# 180221_touchcircuit-2x1011.net
KiCad netlist of a schematic drawn in EAGLE
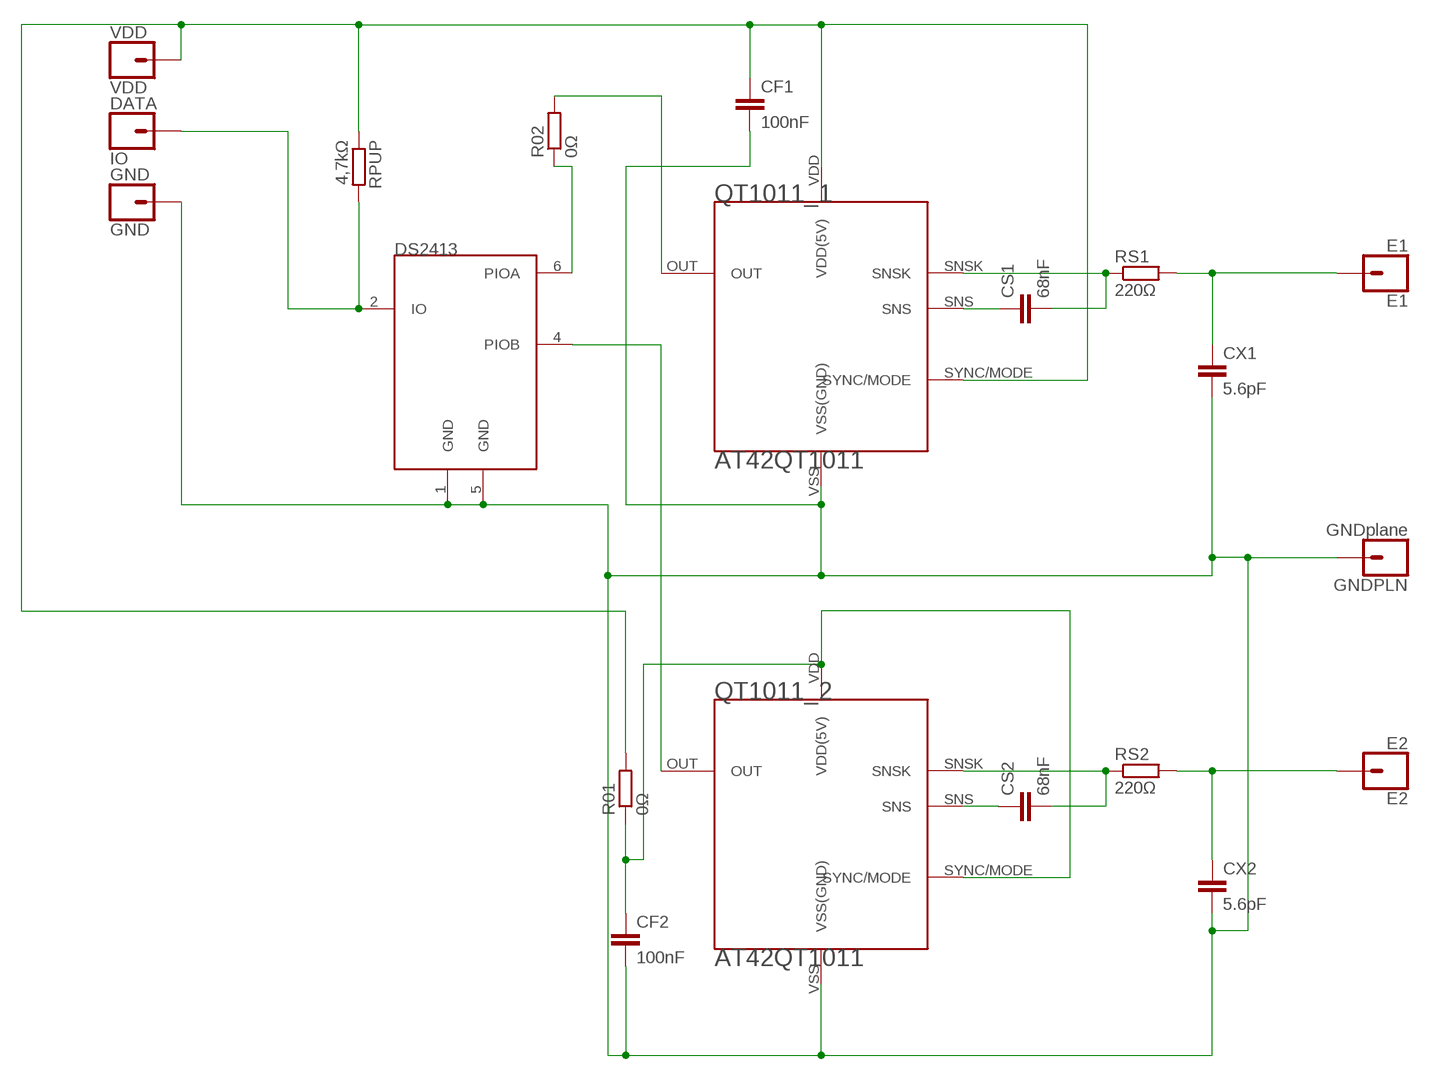
[diagram p0: schematic, sheet 1]

(export (version "E")
  (design (tool "Eeschema 10.0.6"))
  (components
    (comp (ref "CF1")
      (value "100nF")
      (footprint "eagle-import:C1206")
      (libsource (lib "eagle-import") (part "CC1206"))
    )
    (comp (ref "CF2")
      (value "100nF")
      (footprint "eagle-import:C1206")
      (libsource (lib "eagle-import") (part "CC1206"))
    )
    (comp (ref "CS1")
      (value "68nF")
      (footprint "eagle-import:C1206")
      (libsource (lib "eagle-import") (part "CC1206"))
    )
    (comp (ref "CS2")
      (value "68nF")
      (footprint "eagle-import:C1206")
      (libsource (lib "eagle-import") (part "CC1206"))
    )
    (comp (ref "CX1")
      (value "5.6pF")
      (footprint "eagle-import:C1206")
      (libsource (lib "eagle-import") (part "CC1206"))
    )
    (comp (ref "CX2")
      (value "5.6pF")
      (footprint "eagle-import:C1206")
      (libsource (lib "eagle-import") (part "CC1206"))
    )
    (comp (ref "DATA")
      (value "IO")
      (footprint "eagle-import:1X01")
      (libsource (lib "eagle-import") (part "CONN_01"))
    )
    (comp (ref "DS2413")
      (value "DS2413(TSOC6)")
      (footprint "eagle-import:TSOC6")
      (libsource (lib "eagle-import") (part "DS2413(TSOC6)"))
    )
    (comp (ref "E1")
      (value "E1")
      (footprint "eagle-import:1X01")
      (libsource (lib "eagle-import") (part "CONN_01"))
    )
    (comp (ref "E2")
      (value "E2")
      (footprint "eagle-import:1X01")
      (libsource (lib "eagle-import") (part "CONN_01"))
    )
    (comp (ref "GND")
      (value "GND")
      (footprint "eagle-import:1X01")
      (libsource (lib "eagle-import") (part "CONN_01"))
    )
    (comp (ref "GNDPLN")
      (value "GNDplane")
      (footprint "eagle-import:1X01")
      (libsource (lib "eagle-import") (part "CONN_01"))
    )
    (comp (ref "QT1011_1")
      (value "AT42QT1011")
      (footprint "eagle-import:AT42QT1011")
      (libsource (lib "eagle-import") (part "AT42QT1011"))
    )
    (comp (ref "QT1011_2")
      (value "AT42QT1011")
      (footprint "eagle-import:AT42QT1011")
      (libsource (lib "eagle-import") (part "AT42QT1011"))
    )
    (comp (ref "R01")
      (value "0Ω")
      (footprint "eagle-import:R1206")
      (libsource (lib "eagle-import") (part "RR1206"))
    )
    (comp (ref "R02")
      (value "0Ω")
      (footprint "eagle-import:R1206")
      (libsource (lib "eagle-import") (part "RR1206"))
    )
    (comp (ref "RPUP")
      (value "4,7kΩ")
      (footprint "eagle-import:R1206")
      (libsource (lib "eagle-import") (part "RR1206"))
    )
    (comp (ref "RS1")
      (value "220Ω")
      (footprint "eagle-import:R1206")
      (libsource (lib "eagle-import") (part "RR1206"))
    )
    (comp (ref "RS2")
      (value "220Ω")
      (footprint "eagle-import:R1206")
      (libsource (lib "eagle-import") (part "RR1206"))
    )
    (comp (ref "VDD")
      (value "VDD")
      (footprint "eagle-import:1X01")
      (libsource (lib "eagle-import") (part "CONN_01"))
    )
  )
  (nets
    (net (code "1") (name "Net-(CS1-Pad1)") (class "Default")
      (node (ref "CS1") (pin "1") (pinfunction "1_1") (pintype "passive"))
      (node (ref "QT1011_1") (pin "SNS") (pinfunction "SNS_SNS") (pintype "input"))
    )
    (net (code "2") (name "Net-(CS1-Pad2)") (class "Default")
      (node (ref "CS1") (pin "2") (pinfunction "2_2") (pintype "passive"))
      (node (ref "QT1011_1") (pin "SNSK") (pinfunction "SNSK_SNSK") (pintype "input"))
      (node (ref "RS1") (pin "1") (pinfunction "1_1") (pintype "passive"))
    )
    (net (code "3") (name "Net-(CS2-Pad1)") (class "Default")
      (node (ref "CS2") (pin "1") (pinfunction "1_1") (pintype "passive"))
      (node (ref "QT1011_2") (pin "SNS") (pinfunction "SNS_SNS") (pintype "input"))
    )
    (net (code "4") (name "Net-(CS2-Pad2)") (class "Default")
      (node (ref "CS2") (pin "2") (pinfunction "2_2") (pintype "passive"))
      (node (ref "QT1011_2") (pin "SNSK") (pinfunction "SNSK_SNSK") (pintype "input"))
      (node (ref "RS2") (pin "1") (pinfunction "1_1") (pintype "passive"))
    )
    (net (code "5") (name "Net-(CX1-Pad1)") (class "Default")
      (node (ref "CX1") (pin "1") (pinfunction "1_1") (pintype "passive"))
      (node (ref "E1") (pin "1") (pinfunction "1_1") (pintype "passive"))
      (node (ref "RS1") (pin "2") (pinfunction "2_2") (pintype "passive"))
    )
    (net (code "6") (name "Net-(CX2-Pad1)") (class "Default")
      (node (ref "CX2") (pin "1") (pinfunction "1_1") (pintype "passive"))
      (node (ref "E2") (pin "1") (pinfunction "1_1") (pintype "passive"))
      (node (ref "RS2") (pin "2") (pinfunction "2_2") (pintype "passive"))
    )
    (net (code "7") (name "Net-(DS2413-IO)") (class "Default")
      (node (ref "DATA") (pin "1") (pinfunction "1_1") (pintype "passive"))
      (node (ref "DS2413") (pin "2") (pinfunction "IO_2") (pintype "bidirectional"))
      (node (ref "RPUP") (pin "2") (pinfunction "2_2") (pintype "passive"))
    )
    (net (code "8") (name "Net-(DS2413-PIOA)") (class "Default")
      (node (ref "DS2413") (pin "6") (pinfunction "PIOA_6") (pintype "bidirectional"))
      (node (ref "R02") (pin "1") (pinfunction "1_1") (pintype "passive"))
    )
    (net (code "9") (name "Net-(DS2413-PIOB)") (class "Default")
      (node (ref "DS2413") (pin "4") (pinfunction "PIOB_4") (pintype "bidirectional"))
      (node (ref "QT1011_2") (pin "OUT") (pinfunction "OUT_OUT") (pintype "output"))
    )
    (net (code "10") (name "Net-(QT1011_1-PadOUT)") (class "Default")
      (node (ref "QT1011_1") (pin "OUT") (pinfunction "OUT_OUT") (pintype "output"))
      (node (ref "R02") (pin "2") (pinfunction "2_2") (pintype "passive"))
    )
    (net (code "11") (name "Net-(QT1011_1-VDD(5V))") (class "Default")
      (node (ref "CF1") (pin "1") (pinfunction "1_1") (pintype "passive"))
      (node (ref "QT1011_1") (pin "SYNC/MODE") (pinfunction "SYNC/MODE_SYNC/MODE") (pintype "input"))
      (node (ref "QT1011_1") (pin "VDD") (pinfunction "VDD(5V)_VDD") (pintype "power_in"))
      (node (ref "R01") (pin "2") (pinfunction "2_2") (pintype "passive"))
      (node (ref "RPUP") (pin "1") (pinfunction "1_1") (pintype "passive"))
      (node (ref "VDD") (pin "1") (pinfunction "1_1") (pintype "passive"))
    )
    (net (code "12") (name "Net-(QT1011_1-VSS(GND))") (class "Default")
      (node (ref "CF1") (pin "2") (pinfunction "2_2") (pintype "passive"))
      (node (ref "CF2") (pin "2") (pinfunction "2_2") (pintype "passive"))
      (node (ref "CX1") (pin "2") (pinfunction "2_2") (pintype "passive"))
      (node (ref "CX2") (pin "2") (pinfunction "2_2") (pintype "passive"))
      (node (ref "DS2413") (pin "1") (pinfunction "GND_1") (pintype "power_in"))
      (node (ref "DS2413") (pin "5") (pinfunction "GND_5") (pintype "power_in"))
      (node (ref "GND") (pin "1") (pinfunction "1_1") (pintype "passive"))
      (node (ref "GNDPLN") (pin "1") (pinfunction "1_1") (pintype "passive"))
      (node (ref "QT1011_1") (pin "VSS") (pinfunction "VSS(GND)_VSS") (pintype "power_in"))
      (node (ref "QT1011_2") (pin "VSS") (pinfunction "VSS(GND)_VSS") (pintype "power_in"))
    )
    (net (code "13") (name "Net-(QT1011_2-VDD(5V))") (class "Default")
      (node (ref "CF2") (pin "1") (pinfunction "1_1") (pintype "passive"))
      (node (ref "QT1011_2") (pin "SYNC/MODE") (pinfunction "SYNC/MODE_SYNC/MODE") (pintype "input"))
      (node (ref "QT1011_2") (pin "VDD") (pinfunction "VDD(5V)_VDD") (pintype "power_in"))
      (node (ref "R01") (pin "1") (pinfunction "1_1") (pintype "passive"))
    )
  )
)
